# OK1050-C_1_2_Camera.net
KiCad netlist of a schematic drawn in Altium Designer
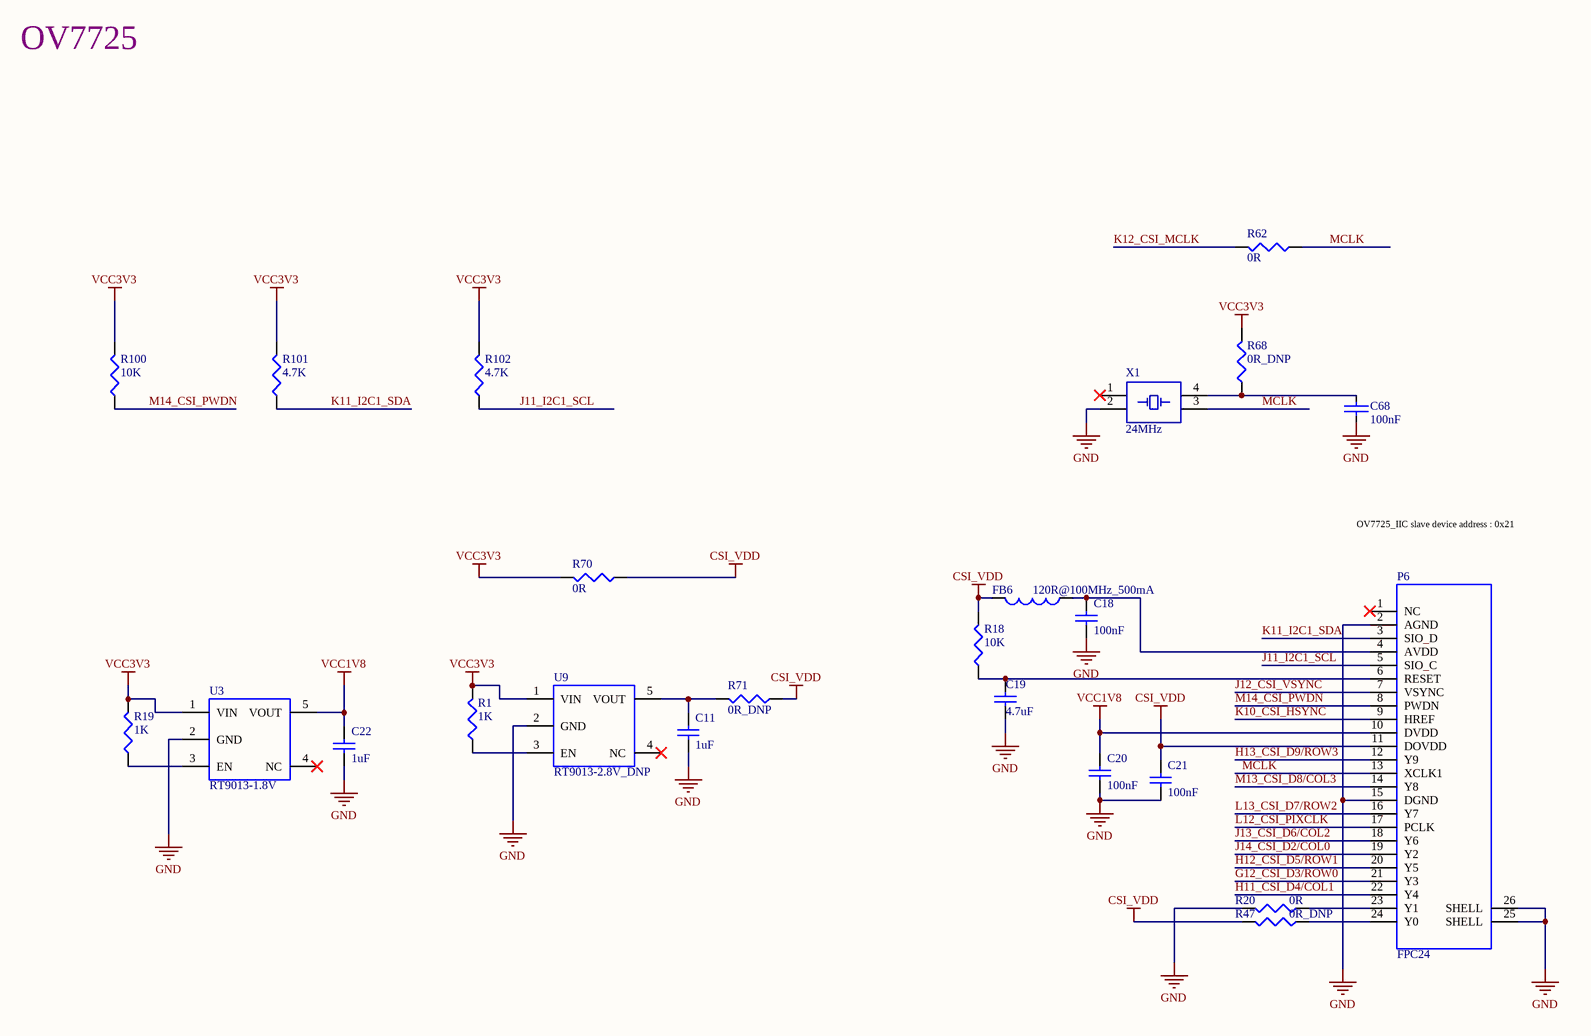
[diagram p0: OK1050-C_1.2_Camera.SchDoc]

(export (version "E")
  (design (tool "Eeschema 10.0.6"))
  (components
    (comp (ref "C11")
      (value "1uF")
      (footprint "0603C+")
      (description "Capacitor")
      (fields (field (name "PUBLISHER") "Altium Limited"))
      (libsource (lib "Miscellaneous Devices") (part "Cap"))
    )
    (comp (ref "C18")
      (value "100nF")
      (footprint "0603C+")
      (description "Capacitor")
      (fields (field (name "PUBLISHER") "Altium Limited"))
      (libsource (lib "Miscellaneous Devices") (part "Cap"))
    )
    (comp (ref "C19")
      (value "4.7uF")
      (footprint "0603C+")
      (description "Capacitor")
      (fields (field (name "Comment") "0.1uF") (field (name "PUBLISHER") "Altium Limited"))
      (libsource (lib "Miscellaneous Devices") (part "Cap"))
    )
    (comp (ref "C20")
      (value "100nF")
      (footprint "0603C+")
      (description "Capacitor")
      (fields (field (name "Comment") "0.1uF") (field (name "PUBLISHER") "Altium Limited"))
      (libsource (lib "Miscellaneous Devices") (part "Cap"))
    )
    (comp (ref "C21")
      (value "100nF")
      (footprint "0603C+")
      (description "Capacitor")
      (fields (field (name "PUBLISHER") "Altium Limited"))
      (libsource (lib "Miscellaneous Devices") (part "Cap"))
    )
    (comp (ref "C22")
      (value "1uF")
      (footprint "0603C+")
      (description "Capacitor")
      (fields (field (name "PUBLISHER") "Altium Limited"))
      (libsource (lib "Miscellaneous Devices") (part "Cap"))
    )
    (comp (ref "C68")
      (value "100nF")
      (footprint "0603C+")
      (libsource (lib "SMARTCORTEX M3-1700_1") (part "CAP_1"))
    )
    (comp (ref "FB6")
      (value "120R@100MHz_500mA")
      (footprint "0603R+")
      (description "Inductor")
      (fields (field (name "PUBLISHER") "Altium Limited"))
      (libsource (lib "Miscellaneous Devices") (part "Inductor"))
    )
    (comp (ref "P6") (value "FPC24") (footprint "FPC24") (libsource (lib "PCB_RT1052") (part "CON24")))
    (comp (ref "R1")
      (value "1K")
      (footprint "0603R+")
      (description "Resistor")
      (fields (field (name "PUBLISHER") "Altium Limited"))
      (libsource (lib "Miscellaneous Devices") (part "Res3"))
    )
    (comp (ref "R18")
      (value "10K")
      (footprint "0603R+")
      (description "Resistor")
      (fields (field (name "PUBLISHER") "Altium Limited"))
      (libsource (lib "Miscellaneous Devices") (part "Res3"))
    )
    (comp (ref "R19")
      (value "1K")
      (footprint "0603R+")
      (description "Resistor")
      (fields (field (name "PUBLISHER") "Altium Limited"))
      (libsource (lib "Miscellaneous Devices") (part "Res3"))
    )
    (comp (ref "R20")
      (value "0R")
      (footprint "0603R+")
      (description "Resistor")
      (fields (field (name "PUBLISHER") "Altium Limited"))
      (libsource (lib "Miscellaneous Devices") (part "Res3"))
    )
    (comp (ref "R47")
      (value "0R_DNP")
      (footprint "0603R+")
      (description "Resistor")
      (fields (field (name "PUBLISHER") "Altium Limited"))
      (libsource (lib "Miscellaneous Devices") (part "Res3"))
    )
    (comp (ref "R62")
      (value "0R")
      (footprint "0603R+")
      (description "Resistor")
      (fields (field (name "PUBLISHER") "Altium Limited"))
      (libsource (lib "Miscellaneous Devices") (part "Res3"))
    )
    (comp (ref "R68")
      (value "0R_DNP")
      (footprint "0603R+")
      (description "Resistor")
      (fields (field (name "PUBLISHER") "Altium Limited"))
      (libsource (lib "Miscellaneous Devices") (part "Res3"))
    )
    (comp (ref "R70")
      (value "0R")
      (footprint "0603R+")
      (description "Resistor")
      (fields (field (name "PUBLISHER") "Altium Limited"))
      (libsource (lib "Miscellaneous Devices") (part "Res3"))
    )
    (comp (ref "R71")
      (value "0R_DNP")
      (footprint "0603R+")
      (description "Resistor")
      (fields (field (name "PUBLISHER") "Altium Limited"))
      (libsource (lib "Miscellaneous Devices") (part "Res3"))
    )
    (comp (ref "R100")
      (value "10K")
      (footprint "0603R+")
      (description "Resistor")
      (fields (field (name "PUBLISHER") "Altium Limited"))
      (libsource (lib "Miscellaneous Devices") (part "Res3"))
    )
    (comp (ref "R101")
      (value "4.7K")
      (footprint "0603R+")
      (description "Resistor")
      (fields (field (name "PUBLISHER") "Altium Limited"))
      (libsource (lib "Miscellaneous Devices") (part "Res3"))
    )
    (comp (ref "R102")
      (value "4.7K")
      (footprint "0603R+")
      (description "Resistor")
      (fields (field (name "PUBLISHER") "Altium Limited"))
      (libsource (lib "Miscellaneous Devices") (part "Res3"))
    )
    (comp (ref "U3")
      (value "RT9013-1.8V")
      (footprint "SOT95P280X129-5N")
      (libsource (lib "IMX6QP-C") (part "RT9013"))
    )
    (comp (ref "U9")
      (value "RT9013-2.8V_DNP")
      (footprint "SOT95P280X129-5N")
      (libsource (lib "IMX6QP-C") (part "RT9013"))
    )
    (comp (ref "X1")
      (value "24MHz")
      (footprint "CRYSTALS_3225SP")
      (libsource (lib "OK5718") (part "oscillator_4PINsp"))
    )
  )
  (nets
    (net (code "1") (name "/G12_CSI_D3{slash}ROW0") (class "Default")
      (node (ref "P6") (pin "21") (pinfunction "Y3_21") (pintype "passive"))
    )
    (net (code "2") (name "/H11_CSI_D4{slash}COL1") (class "Default")
      (node (ref "P6") (pin "22") (pinfunction "Y4_22") (pintype "passive"))
    )
    (net (code "3") (name "/H12_CSI_D5{slash}ROW1") (class "Default")
      (node (ref "P6") (pin "20") (pinfunction "Y5_20") (pintype "passive"))
    )
    (net (code "4") (name "/H13_CSI_D9{slash}ROW3") (class "Default")
      (node (ref "P6") (pin "12") (pinfunction "Y9_12") (pintype "passive"))
    )
    (net (code "5") (name "/J11_I2C1_SCL") (class "Default")
      (node (ref "P6") (pin "5") (pinfunction "SIO_C_5") (pintype "passive"))
      (node (ref "R102") (pin "1") (pinfunction "1_1") (pintype "passive"))
    )
    (net (code "6") (name "/J12_CSI_VSYNC") (class "Default")
      (node (ref "P6") (pin "7") (pinfunction "VSYNC_7") (pintype "passive"))
    )
    (net (code "7") (name "/J13_CSI_D6{slash}COL2") (class "Default")
      (node (ref "P6") (pin "18") (pinfunction "Y6_18") (pintype "passive"))
    )
    (net (code "8") (name "/J14_CSI_D2{slash}COL0") (class "Default")
      (node (ref "P6") (pin "19") (pinfunction "Y2_19") (pintype "passive"))
    )
    (net (code "9") (name "/K10_CSI_HSYNC") (class "Default")
      (node (ref "P6") (pin "9") (pinfunction "HREF_9") (pintype "passive"))
    )
    (net (code "10") (name "/K11_I2C1_SDA") (class "Default")
      (node (ref "P6") (pin "3") (pinfunction "SIO_D_3") (pintype "passive"))
      (node (ref "R101") (pin "1") (pinfunction "1_1") (pintype "passive"))
    )
    (net (code "11") (name "/K12_CSI_MCLK") (class "Default")
      (node (ref "R62") (pin "2") (pinfunction "2_2") (pintype "passive"))
    )
    (net (code "12") (name "/L12_CSI_PIXCLK") (class "Default")
      (node (ref "P6") (pin "17") (pinfunction "PCLK_17") (pintype "passive"))
    )
    (net (code "13") (name "/L13_CSI_D7{slash}ROW2") (class "Default")
      (node (ref "P6") (pin "16") (pinfunction "Y7_16") (pintype "passive"))
    )
    (net (code "14") (name "/M13_CSI_D8{slash}COL3") (class "Default")
      (node (ref "P6") (pin "14") (pinfunction "Y8_14") (pintype "passive"))
    )
    (net (code "15") (name "/M14_CSI_PWDN") (class "Default")
      (node (ref "P6") (pin "8") (pinfunction "PWDN_8") (pintype "passive"))
      (node (ref "R100") (pin "1") (pinfunction "1_1") (pintype "passive"))
    )
    (net (code "16") (name "/MCLK") (class "Default")
      (node (ref "P6") (pin "13") (pinfunction "XCLK1_13") (pintype "passive"))
      (node (ref "R62") (pin "1") (pinfunction "1_1") (pintype "passive"))
      (node (ref "X1") (pin "3") (pintype "passive"))
    )
    (net (code "17") (name "CSI_VDD") (class "Default")
      (node (ref "C21") (pin "1") (pinfunction "1_1") (pintype "passive"))
      (node (ref "FB6") (pin "2") (pinfunction "2_2") (pintype "passive"))
      (node (ref "P6") (pin "11") (pinfunction "DOVDD_11") (pintype "passive"))
      (node (ref "R18") (pin "2") (pinfunction "2_2") (pintype "passive"))
      (node (ref "R47") (pin "2") (pinfunction "2_2") (pintype "passive"))
      (node (ref "R70") (pin "1") (pinfunction "1_1") (pintype "passive"))
      (node (ref "R71") (pin "1") (pinfunction "1_1") (pintype "passive"))
    )
    (net (code "18") (name "GND") (class "Default")
      (node (ref "C11") (pin "1") (pinfunction "1_1") (pintype "passive"))
      (node (ref "C18") (pin "2") (pinfunction "2_2") (pintype "passive"))
      (node (ref "C19") (pin "2") (pinfunction "2_2") (pintype "passive"))
      (node (ref "C20") (pin "2") (pinfunction "2_2") (pintype "passive"))
      (node (ref "C21") (pin "2") (pinfunction "2_2") (pintype "passive"))
      (node (ref "C22") (pin "1") (pinfunction "1_1") (pintype "passive"))
      (node (ref "C68") (pin "1") (pintype "passive"))
      (node (ref "P6") (pin "15") (pinfunction "DGND_15") (pintype "passive"))
      (node (ref "P6") (pin "2") (pinfunction "AGND_2") (pintype "passive"))
      (node (ref "P6") (pin "25") (pinfunction "SHELL_25") (pintype "passive"))
      (node (ref "P6") (pin "26") (pinfunction "SHELL_26") (pintype "passive"))
      (node (ref "R20") (pin "2") (pinfunction "2_2") (pintype "passive"))
      (node (ref "U3") (pin "2") (pinfunction "GND_2") (pintype "passive"))
      (node (ref "U9") (pin "2") (pinfunction "GND_2") (pintype "passive"))
      (node (ref "X1") (pin "2") (pintype "passive"))
    )
    (net (code "19") (name "Net-(C68-Pad2)") (class "Default")
      (node (ref "C68") (pin "2") (pintype "passive"))
      (node (ref "R68") (pin "1") (pinfunction "1_1") (pintype "passive"))
      (node (ref "X1") (pin "4") (pintype "passive"))
    )
    (net (code "20") (name "Net-(P6-AVDD)") (class "Default")
      (node (ref "C18") (pin "1") (pinfunction "1_1") (pintype "passive"))
      (node (ref "FB6") (pin "1") (pinfunction "1_1") (pintype "passive"))
      (node (ref "P6") (pin "4") (pinfunction "AVDD_4") (pintype "passive"))
    )
    (net (code "21") (name "Net-(P6-RESET)") (class "Default")
      (node (ref "C19") (pin "1") (pinfunction "1_1") (pintype "passive"))
      (node (ref "P6") (pin "6") (pinfunction "RESET_6") (pintype "passive"))
      (node (ref "R18") (pin "1") (pinfunction "1_1") (pintype "passive"))
    )
    (net (code "22") (name "Net-(P6-Y0)") (class "Default")
      (node (ref "P6") (pin "24") (pinfunction "Y0_24") (pintype "passive"))
      (node (ref "R47") (pin "1") (pinfunction "1_1") (pintype "passive"))
    )
    (net (code "23") (name "Net-(P6-Y1)") (class "Default")
      (node (ref "P6") (pin "23") (pinfunction "Y1_23") (pintype "passive"))
      (node (ref "R20") (pin "1") (pinfunction "1_1") (pintype "passive"))
    )
    (net (code "24") (name "Net-(U3-EN)") (class "Default")
      (node (ref "R19") (pin "1") (pinfunction "1_1") (pintype "passive"))
      (node (ref "U3") (pin "3") (pinfunction "EN_3") (pintype "passive"))
    )
    (net (code "25") (name "Net-(U9-EN)") (class "Default")
      (node (ref "R1") (pin "1") (pinfunction "1_1") (pintype "passive"))
      (node (ref "U9") (pin "3") (pinfunction "EN_3") (pintype "passive"))
    )
    (net (code "26") (name "Net-(U9-VOUT)") (class "Default")
      (node (ref "C11") (pin "2") (pinfunction "2_2") (pintype "passive"))
      (node (ref "R71") (pin "2") (pinfunction "2_2") (pintype "passive"))
      (node (ref "U9") (pin "5") (pinfunction "VOUT_5") (pintype "passive"))
    )
    (net (code "27") (name "VCC1V8") (class "Default")
      (node (ref "C20") (pin "1") (pinfunction "1_1") (pintype "passive"))
      (node (ref "C22") (pin "2") (pinfunction "2_2") (pintype "passive"))
      (node (ref "P6") (pin "10") (pinfunction "DVDD_10") (pintype "passive"))
      (node (ref "U3") (pin "5") (pinfunction "VOUT_5") (pintype "passive"))
    )
    (net (code "28") (name "VCC3V3") (class "Default")
      (node (ref "R1") (pin "2") (pinfunction "2_2") (pintype "passive"))
      (node (ref "R100") (pin "2") (pinfunction "2_2") (pintype "passive"))
      (node (ref "R101") (pin "2") (pinfunction "2_2") (pintype "passive"))
      (node (ref "R102") (pin "2") (pinfunction "2_2") (pintype "passive"))
      (node (ref "R19") (pin "2") (pinfunction "2_2") (pintype "passive"))
      (node (ref "R68") (pin "2") (pinfunction "2_2") (pintype "passive"))
      (node (ref "R70") (pin "2") (pinfunction "2_2") (pintype "passive"))
      (node (ref "U3") (pin "1") (pinfunction "VIN_1") (pintype "passive"))
      (node (ref "U9") (pin "1") (pinfunction "VIN_1") (pintype "passive"))
    )
    (net (code "29") (name "unconnected-(P6-NC-Pad1)") (class "Default")
      (node (ref "P6") (pin "1") (pinfunction "NC_1") (pintype "passive+no_connect"))
    )
    (net (code "30") (name "unconnected-(U3-NC-Pad4)") (class "Default")
      (node (ref "U3") (pin "4") (pinfunction "NC_4") (pintype "passive+no_connect"))
    )
    (net (code "31") (name "unconnected-(U9-NC-Pad4)") (class "Default")
      (node (ref "U9") (pin "4") (pinfunction "NC_4") (pintype "passive+no_connect"))
    )
    (net (code "32") (name "unconnected-(X1-Pad1)") (class "Default")
      (node (ref "X1") (pin "1") (pintype "passive+no_connect"))
    )
  )
)
